# master_node_v0_1.net
KiCad netlist of a schematic drawn in EAGLE
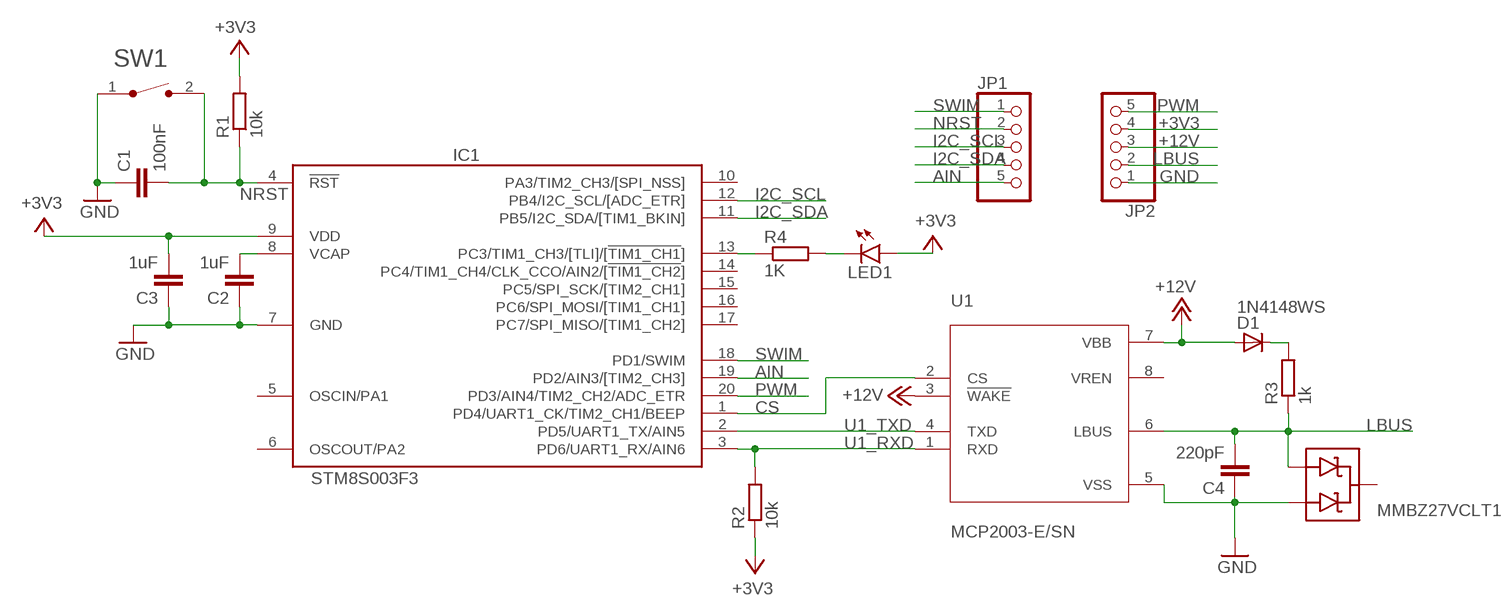
[diagram p0: schematic, sheet 1]

(export (version "E")
  (design (tool "Eeschema 10.0.6"))
  (components
    (comp (ref "C1")
      (value "100nF")
      (footprint "eagle-import:C0603")
      (libsource (lib "eagle-import") (part "C-EUC0603"))
    )
    (comp (ref "C2")
      (value "1uF")
      (footprint "eagle-import:C0603")
      (libsource (lib "eagle-import") (part "C-EUC0603"))
    )
    (comp (ref "C3")
      (value "1uF")
      (footprint "eagle-import:C0603")
      (libsource (lib "eagle-import") (part "C-EUC0603"))
    )
    (comp (ref "C4")
      (value "220pF")
      (footprint "eagle-import:C0603")
      (libsource (lib "eagle-import") (part "C-EUC0603"))
    )
    (comp (ref "D1")
      (value "1N4148WS")
      (footprint "eagle-import:SOD323")
      (fields (field (name "MF") "ON Semiconductor"))
      (libsource (lib "eagle-import") (part "1N4148WS"))
    )
    (comp (ref "D2")
      (value "MMBZ27VCLT1")
      (footprint "eagle-import:SOT23-3")
      (fields (field (name "MF") "ON Semiconductor") (field (name "SPICEPREFIX") "U"))
      (libsource (lib "eagle-import") (part "MMBZ27VCLT1"))
    )
    (comp (ref "IC1")
      (value "STM8S003F3")
      (footprint "eagle-import:TSSOP20")
      (libsource (lib "eagle-import") (part "STM8S003F3"))
    )
    (comp (ref "JP1")
      (value "PINHD-1X5")
      (footprint "eagle-import:1X05")
      (libsource (lib "eagle-import") (part "PINHD-1X5"))
    )
    (comp (ref "JP2")
      (value "PINHD-1X5")
      (footprint "eagle-import:1X05")
      (libsource (lib "eagle-import") (part "PINHD-1X5"))
    )
    (comp (ref "LED1")
      (value "LEDCHIP-LED0603")
      (footprint "eagle-import:CHIP-LED0603")
      (libsource (lib "eagle-import") (part "LEDCHIP-LED0603"))
    )
    (comp (ref "R1")
      (value "10k")
      (footprint "eagle-import:R0603")
      (libsource (lib "eagle-import") (part "R-EU_R0603"))
    )
    (comp (ref "R2")
      (value "10k")
      (footprint "eagle-import:R0603")
      (libsource (lib "eagle-import") (part "R-EU_R0603"))
    )
    (comp (ref "R3")
      (value "1k")
      (footprint "eagle-import:R0603")
      (libsource (lib "eagle-import") (part "R-EU_R0603"))
    )
    (comp (ref "R4")
      (value "1K")
      (footprint "eagle-import:R0603")
      (libsource (lib "eagle-import") (part "R-EU_R0603"))
    )
    (comp (ref "SW1")
      (value "FSMSM")
      (footprint "eagle-import:TE_FSMSM")
      (fields (field (name "COMMENT") "1437566-3") (field (name "MF") "TE Connectivity"))
      (libsource (lib "eagle-import") (part "FSMSM"))
    )
    (comp (ref "U1")
      (value "MCP2003-E/SN")
      (footprint "eagle-import:SOIC127P600X175-8N")
      (fields (field (name "MF") "Microchip"))
      (libsource (lib "eagle-import") (part "MCP2003-E/SN"))
    )
  )
  (nets
    (net (code "1") (name "+3V3") (class "Default")
      (node (ref "C3") (pin "2") (pinfunction "2_2") (pintype "passive"))
      (node (ref "IC1") (pin "9") (pinfunction "VDD_9") (pintype "power_in"))
      (node (ref "JP2") (pin "4") (pinfunction "4_4") (pintype "passive"))
      (node (ref "LED1") (pin "A") (pinfunction "A_A") (pintype "passive"))
      (node (ref "R1") (pin "2") (pinfunction "2_2") (pintype "passive"))
      (node (ref "R2") (pin "1") (pinfunction "1_1") (pintype "passive"))
    )
    (net (code "2") (name "+12V") (class "Default")
      (node (ref "D1") (pin "A") (pinfunction "A_A") (pintype "passive"))
      (node (ref "JP2") (pin "3") (pinfunction "3_3") (pintype "passive"))
      (node (ref "U1") (pin "3") (pinfunction "~{WAKE}_3") (pintype "input"))
      (node (ref "U1") (pin "7") (pinfunction "VBB_7") (pintype "power_in"))
    )
    (net (code "3") (name "/AIN") (class "Default")
      (node (ref "IC1") (pin "19") (pinfunction "PD2/AIN3/[TIM2_CH3]_19") (pintype "bidirectional"))
      (node (ref "JP1") (pin "5") (pinfunction "5_5") (pintype "passive"))
    )
    (net (code "4") (name "/CS") (class "Default")
      (node (ref "IC1") (pin "1") (pinfunction "PD4/UART1_CK/TIM2_CH1/BEEP_1") (pintype "bidirectional"))
      (node (ref "U1") (pin "2") (pinfunction "CS_2") (pintype "input"))
    )
    (net (code "5") (name "/I2C_SCL") (class "Default")
      (node (ref "IC1") (pin "12") (pinfunction "PB4/I2C_SCL/[ADC_ETR]_12") (pintype "bidirectional"))
      (node (ref "JP1") (pin "3") (pinfunction "3_3") (pintype "passive"))
    )
    (net (code "6") (name "/I2C_SDA") (class "Default")
      (node (ref "IC1") (pin "11") (pinfunction "PB5/I2C_SDA/[TIM1_BKIN]_11") (pintype "bidirectional"))
      (node (ref "JP1") (pin "4") (pinfunction "4_4") (pintype "passive"))
    )
    (net (code "7") (name "/LBUS") (class "Default")
      (node (ref "C4") (pin "2") (pinfunction "2_2") (pintype "passive"))
      (node (ref "D2") (pin "2") (pinfunction "A2_2") (pintype "passive"))
      (node (ref "JP2") (pin "2") (pinfunction "2_2") (pintype "passive"))
      (node (ref "R3") (pin "1") (pinfunction "1_1") (pintype "passive"))
      (node (ref "U1") (pin "6") (pinfunction "LBUS_6") (pintype "bidirectional"))
    )
    (net (code "8") (name "/NRST") (class "Default")
      (node (ref "C1") (pin "2") (pinfunction "2_2") (pintype "passive"))
      (node (ref "IC1") (pin "4") (pinfunction "~{RST}_4") (pintype "input"))
      (node (ref "JP1") (pin "2") (pinfunction "2_2") (pintype "passive"))
      (node (ref "R1") (pin "1") (pinfunction "1_1") (pintype "passive"))
      (node (ref "SW1") (pin "2") (pinfunction "2_2") (pintype "passive"))
    )
    (net (code "9") (name "/PWM") (class "Default")
      (node (ref "IC1") (pin "20") (pinfunction "PD3/AIN4/TIM2_CH2/ADC_ETR_20") (pintype "bidirectional"))
      (node (ref "JP2") (pin "5") (pinfunction "5_5") (pintype "passive"))
    )
    (net (code "10") (name "/SWIM") (class "Default")
      (node (ref "IC1") (pin "18") (pinfunction "PD1/SWIM_18") (pintype "bidirectional"))
      (node (ref "JP1") (pin "1") (pinfunction "1_1") (pintype "passive"))
    )
    (net (code "11") (name "/U1_RXD") (class "Default")
      (node (ref "IC1") (pin "3") (pinfunction "PD6/UART1_RX/AIN6_3") (pintype "bidirectional"))
      (node (ref "R2") (pin "2") (pinfunction "2_2") (pintype "passive"))
      (node (ref "U1") (pin "1") (pinfunction "RXD_1") (pintype "output"))
    )
    (net (code "12") (name "/U1_TXD") (class "Default")
      (node (ref "IC1") (pin "2") (pinfunction "PD5/UART1_TX/AIN5_2") (pintype "bidirectional"))
      (node (ref "U1") (pin "4") (pinfunction "TXD_4") (pintype "input"))
    )
    (net (code "13") (name "GND") (class "Default")
      (node (ref "C1") (pin "1") (pinfunction "1_1") (pintype "passive"))
      (node (ref "C2") (pin "1") (pinfunction "1_1") (pintype "passive"))
      (node (ref "C3") (pin "1") (pinfunction "1_1") (pintype "passive"))
      (node (ref "C4") (pin "1") (pinfunction "1_1") (pintype "passive"))
      (node (ref "D2") (pin "1") (pinfunction "A1_1") (pintype "passive"))
      (node (ref "IC1") (pin "7") (pinfunction "GND_7") (pintype "power_in"))
      (node (ref "JP2") (pin "1") (pinfunction "1_1") (pintype "passive"))
      (node (ref "SW1") (pin "1") (pinfunction "1_1") (pintype "passive"))
      (node (ref "U1") (pin "5") (pinfunction "VSS_5") (pintype "power_in"))
    )
    (net (code "14") (name "Net-(D1-PadC)") (class "Default")
      (node (ref "D1") (pin "C") (pinfunction "C_C") (pintype "passive"))
      (node (ref "R3") (pin "2") (pinfunction "2_2") (pintype "passive"))
    )
    (net (code "15") (name "Net-(IC1-PC3{slash}TIM1_CH3{slash}[TLI]{slash}[~{TIM1_CH1}])") (class "Default")
      (node (ref "IC1") (pin "13") (pinfunction "PC3/TIM1_CH3/[TLI]/[~{TIM1_CH1}]_13") (pintype "bidirectional"))
      (node (ref "R4") (pin "1") (pinfunction "1_1") (pintype "passive"))
    )
    (net (code "16") (name "Net-(IC1-VCAP)") (class "Default")
      (node (ref "C2") (pin "2") (pinfunction "2_2") (pintype "passive"))
      (node (ref "IC1") (pin "8") (pinfunction "VCAP_8") (pintype "power_in"))
    )
    (net (code "17") (name "Net-(LED1-PadC)") (class "Default")
      (node (ref "LED1") (pin "C") (pinfunction "C_C") (pintype "passive"))
      (node (ref "R4") (pin "2") (pinfunction "2_2") (pintype "passive"))
    )
    (net (code "18") (name "unconnected-(D2-C-Pad3)") (class "Default")
      (node (ref "D2") (pin "3") (pinfunction "C_3") (pintype "passive"))
    )
    (net (code "19") (name "unconnected-(IC1-OSCIN{slash}PA1-Pad5)") (class "Default")
      (node (ref "IC1") (pin "5") (pinfunction "OSCIN/PA1_5") (pintype "bidirectional"))
    )
    (net (code "20") (name "unconnected-(IC1-OSCOUT{slash}PA2-Pad6)") (class "Default")
      (node (ref "IC1") (pin "6") (pinfunction "OSCOUT/PA2_6") (pintype "bidirectional"))
    )
    (net (code "21") (name "unconnected-(IC1-PA3{slash}TIM2_CH3{slash}[SPI_NSS]-Pad10)") (class "Default")
      (node (ref "IC1") (pin "10") (pinfunction "PA3/TIM2_CH3/[SPI_NSS]_10") (pintype "bidirectional"))
    )
    (net (code "22") (name "unconnected-(IC1-PC4{slash}TIM1_CH4{slash}CLK_CCO{slash}AIN2{slash}[~{TIM1_CH2}]-Pad14)") (class "Default")
      (node (ref "IC1") (pin "14") (pinfunction "PC4/TIM1_CH4/CLK_CCO/AIN2/[~{TIM1_CH2}]_14") (pintype "bidirectional"))
    )
    (net (code "23") (name "unconnected-(IC1-PC5{slash}SPI_SCK{slash}[TIM2_CH1]-Pad15)") (class "Default")
      (node (ref "IC1") (pin "15") (pinfunction "PC5/SPI_SCK/[TIM2_CH1]_15") (pintype "bidirectional"))
    )
    (net (code "24") (name "unconnected-(IC1-PC6{slash}SPI_MOSI{slash}[TIM1_CH1]-Pad16)") (class "Default")
      (node (ref "IC1") (pin "16") (pinfunction "PC6/SPI_MOSI/[TIM1_CH1]_16") (pintype "bidirectional"))
    )
    (net (code "25") (name "unconnected-(IC1-PC7{slash}SPI_MISO{slash}[TIM1_CH2]-Pad17)") (class "Default")
      (node (ref "IC1") (pin "17") (pinfunction "PC7/SPI_MISO/[TIM1_CH2]_17") (pintype "bidirectional"))
    )
    (net (code "26") (name "unconnected-(U1-VREN-Pad8)") (class "Default")
      (node (ref "U1") (pin "8") (pinfunction "VREN_8") (pintype "output"))
    )
  )
)
